# MainSch.net
KiCad netlist of a schematic drawn in Altium Designer
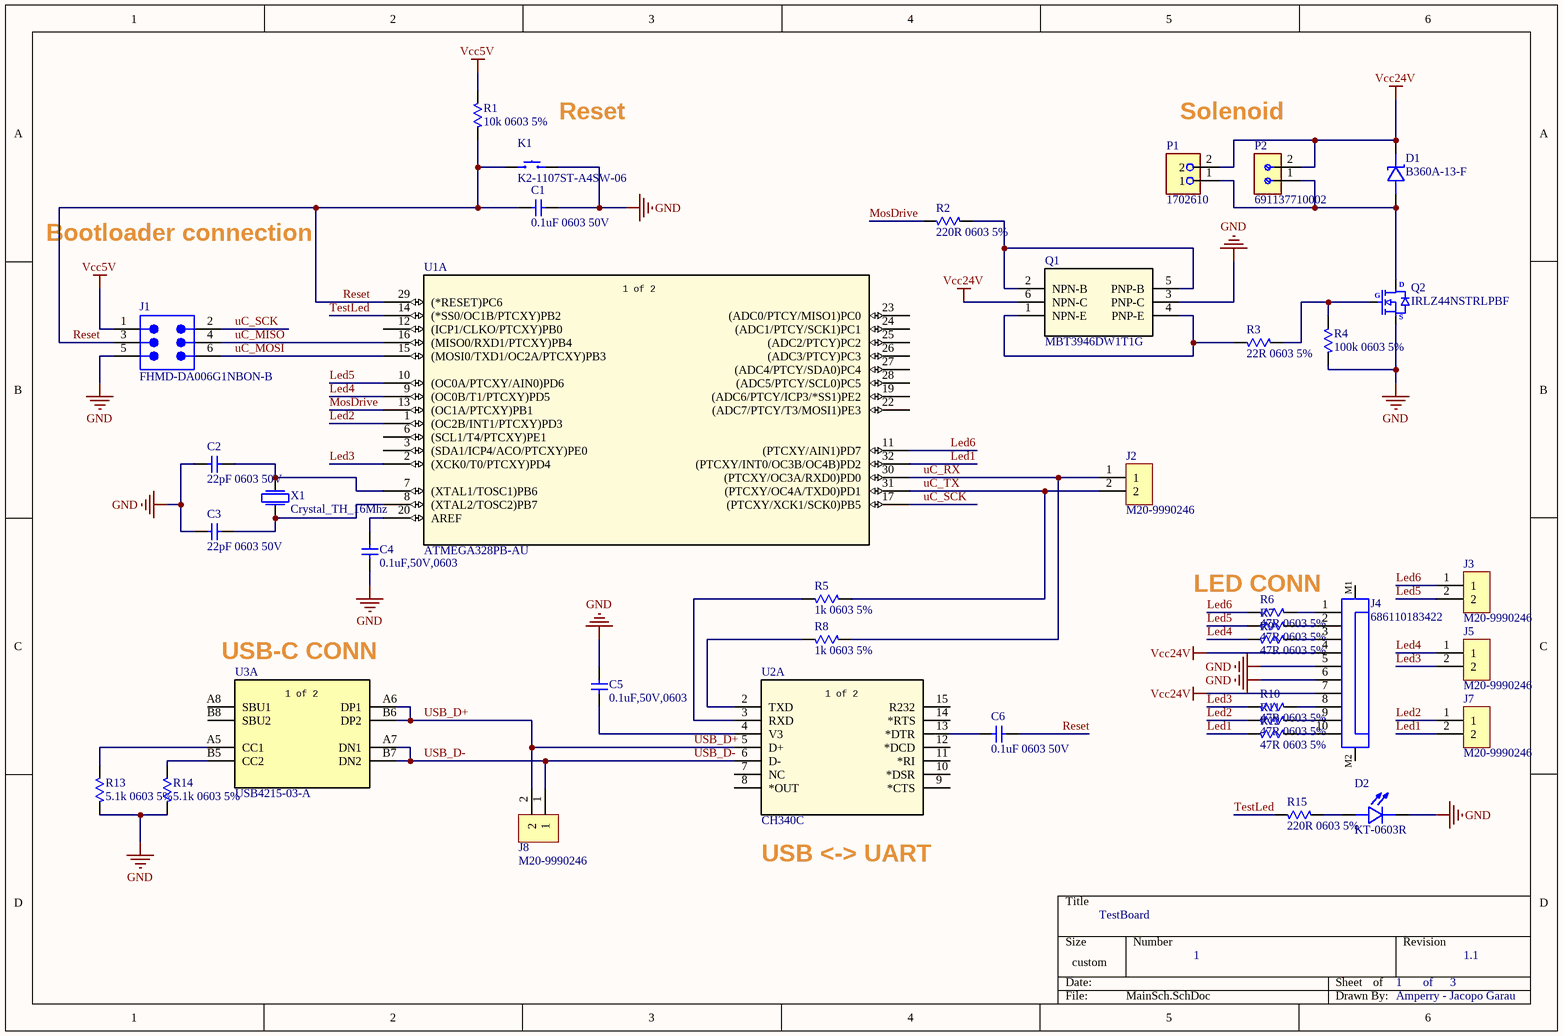
[diagram p0: MainSch.SchDoc]

(export (version "E")
  (design (tool "Eeschema 10.0.6"))
  (components
    (comp (ref "C1")
      (value "0.1uF 0603 50V")
      (footprint "CAP_0603")
      (description "50V 0.1uF (100nF) X7R ±10% 0603 Multilayer Ceramic Capacitors MLCC - SMD/SMT ROHS")
      (fields
        (field (name "MANUFACTURER PART NUMBER") "CL10B104KB8NNNC")
        (field (name "JLCPCB PART NUMBER") "C1591")
      )
      (libsource (lib "Amperry") (part "Capacitor"))
    )
    (comp (ref "C2")
      (value "22pF 0603 50V")
      (footprint "CAP_0603")
      (description "25V 10uF C0G ±5% 0603 Multilayer Ceramic Capacitors MLCC - SMD/SMT ROHS")
      (fields (field (name "VOLTAGE") "50V") (field (name "JLCPCB PART NUMBER") "C2167297"))
      (libsource (lib "Amperry") (part "Capacitor"))
    )
    (comp (ref "C3")
      (value "22pF 0603 50V")
      (footprint "CAP_0603")
      (description "25V 10uF C0G ±5% 0603 Multilayer Ceramic Capacitors MLCC - SMD/SMT ROHS")
      (fields (field (name "VOLTAGE") "50V") (field (name "JLCPCB PART NUMBER") "C2167297"))
      (libsource (lib "Amperry") (part "Capacitor"))
    )
    (comp (ref "C4")
      (value "0.1uF,50V,0603")
      (footprint "CAP_0603")
      (description "50V 0.1uF X7R 10% Pad SMD 0603 125°C T/R Ceramic Capacitor (MLCC")
      (fields
        (field (name "MANUFACTURER") "Samsung Electro-Mechanics")
        (field (name "MANUFACTURER PART NUMBER") "CL10B104KB8NNNC")
      )
      (libsource (lib "My_Integrated_Library") (part "CL10B104KB8NNNC"))
    )
    (comp (ref "C5")
      (value "0.1uF,50V,0603")
      (footprint "CAP_0603")
      (description "50V 0.1uF X7R 10% Pad SMD 0603 125°C T/R Ceramic Capacitor (MLCC")
      (fields
        (field (name "MANUFACTURER") "Samsung Electro-Mechanics")
        (field (name "MANUFACTURER PART NUMBER") "CL10B104KB8NNNC")
      )
      (libsource (lib "My_Integrated_Library") (part "CL10B104KB8NNNC"))
    )
    (comp (ref "C6")
      (value "0.1uF 0603 50V")
      (footprint "CAP_0603")
      (description "50V 0.1uF (100nF) X7R ±10% 0603 Multilayer Ceramic Capacitors MLCC - SMD/SMT ROHS")
      (fields
        (field (name "MANUFACTURER PART NUMBER") "CL10B104KB8NNNC")
        (field (name "JLCPCB PART NUMBER") "C1591")
      )
      (libsource (lib "Amperry") (part "Capacitor"))
    )
    (comp (ref "D1")
      (value "B360A-13-F")
      (footprint "SMA-DO-214AC")
      (description "60V 3.0A SURFACE MOUNT SCHOTTKY BARRIER RECTIFIER")
      (libsource (lib "Amperry") (part "Diode Schottky"))
    )
    (comp (ref "D2")
      (value "KT-0603R")
      (footprint "LED_0603")
      (description "Diode Red 20mA")
      (fields
        (field (name "MANUFACTURER PART NUMBER") "ERJ3GEYJ470V")
        (field (name "JLCPCB PART NUMBER") "C2286")
      )
      (libsource (lib "Amperry") (part "LED"))
    )
    (comp (ref "J1")
      (value "FHMD-DA006G1NBON-B")
      (footprint "Header_Female_2x3_2.54mm")
      (description "Header_Female_2x3_2.54mm")
      (fields
        (field (name "MANUFACTURER") "Sullins")
        (field (name "MANUFACTURER PART NUMBER") "PPTC032LFBN-RC")
      )
      (libsource (lib "Amperry") (part "Header_Female_2x3"))
    )
    (comp (ref "J2")
      (value "M20-9990246")
      (footprint "Header_Male_1x2_2.54mm")
      (description "Header Male 1x2 2.54mm")
      (fields (field (name "JLCPCB PART NUMBER") "C90288") (field (name "MANUFACTURER") "Harwin"))
      (libsource (lib "") (part "Header_Male_1x2_1"))
    )
    (comp (ref "J3")
      (value "M20-9990246")
      (footprint "Header_Male_1x2_2.54mm")
      (description "Header Male 1x2 2.54mm")
      (fields (field (name "JLCPCB PART NUMBER") "C90288") (field (name "MANUFACTURER") "Harwin"))
      (libsource (lib "") (part "Header_Male_1x2_1"))
    )
    (comp (ref "J4")
      (value "686110183422")
      (footprint "686110183422")
      (description "WR-FPC 1.00mm SMT Horiz. Top Cont. Low Profile")
      (fields (field (name "JLCPCB PART NUMBER") "C6095598"))
      (libsource (lib "Amperry") (part "686110183422"))
    )
    (comp (ref "J5")
      (value "M20-9990246")
      (footprint "Header_Male_1x2_2.54mm")
      (description "Header Male 1x2 2.54mm")
      (fields (field (name "JLCPCB PART NUMBER") "C90288") (field (name "MANUFACTURER") "Harwin"))
      (libsource (lib "") (part "Header_Male_1x2_1"))
    )
    (comp (ref "J7")
      (value "M20-9990246")
      (footprint "Header_Male_1x2_2.54mm")
      (description "Header Male 1x2 2.54mm")
      (fields (field (name "JLCPCB PART NUMBER") "C90288") (field (name "MANUFACTURER") "Harwin"))
      (libsource (lib "") (part "Header_Male_1x2_1"))
    )
    (comp (ref "J8")
      (value "M20-9990246")
      (footprint "Header_Male_1x2_2.54mm")
      (description "Header Male 1x2 2.54mm")
      (fields (field (name "JLCPCB PART NUMBER") "C90288") (field (name "MANUFACTURER") "Harwin"))
      (libsource (lib "Amperry") (part "Header_Male_1x2"))
    )
    (comp (ref "K1")
      (value "K2-1107ST-A4SW-06")
      (footprint "K2-1107ST-A4SW-06")
      (fields (field (name "JLCPCB PART NUMBER") "C2837195"))
      (libsource (lib "Amperry") (part "K2-1107ST-A4SW-06"))
    )
    (comp (ref "P1")
      (value "1702610")
      (footprint "1702610")
      (description "Conn PC Terminal Block 2 POS 2.5mm Solder ST Thru-Hole 4A T/R")
      (fields (field (name "VOLTAGE") "150V") (field (name "JLCPCB PART NUMBER") "C21433539"))
      (libsource (lib "Amperry") (part "1702610"))
    )
    (comp (ref "P2")
      (value "691137710002")
      (footprint "Termina_Block_1x2_5mm")
      (description "Terminal Block, 5mm Pitch, Horizontal, Pressure Clamp Glow Wire, Pcb, 2PINS, Gr")
      (fields (field (name "JLCPCB PART NUMBER") "C3703") (field (name "MANUFACTURER") "Wurth Elektronik"))
      (libsource (lib "Amperry") (part "Terminal_Block_1x2"))
    )
    (comp (ref "Q1")
      (value "MBT3946DW1T1G")
      (footprint "SOT-363")
      (description "Dual Npn+Pnp Rf Bipolar Transistor, 0.2 A, 40V, 6-PIN SC-88")
      (fields (field (name "MANUFACTURER") "onsemi") (field (name "JLCPCB PART NUMBER") "C28272"))
      (libsource (lib "Amperry") (part "MBT3946DW1T1G"))
    )
    (comp (ref "Q2")
      (value "IRLZ44NSTRLPBF")
      (footprint "D2PAK")
      (description "Mosfet, Power; N-ch; Vdss 55V; Rds(on) 0.022 Ohm; Id 47A; D2PAK; Pd 110W; Vgs +/-16V; -55")
      (fields (field (name "MANUFACTURER") "Infineon") (field (name "JLCPCB PART NUMBER") "C18212570"))
      (libsource (lib "Amperry") (part "IRLZ44N"))
    )
    (comp (ref "R1")
      (value "10k 0603 5%")
      (footprint "RES_0603")
      (description "10k Ohm 0603 5% Chip Resistor SMD")
      (fields (field (name "TOLERANCE") "5%") (field (name "JLCPCB PART NUMBER") "C25804"))
      (libsource (lib "Amperry") (part "Resistor"))
    )
    (comp (ref "R2")
      (value "220R 0603 5%")
      (footprint "RES_0603")
      (description "220 Ohm 0603 5% Chip Resistor SMD")
      (fields
        (field (name "MANUFACTURER") "Royal Ohm")
        (field (name "MANUFACTURER PART NUMBER") "0603WAJ0221T5E")
      )
      (libsource (lib "Amperry") (part "Resistor"))
    )
    (comp (ref "R3")
      (value "22R 0603 5%")
      (footprint "RES_0603")
      (description "22 Ohm 0603 1% Chip Resistor SMD")
      (fields (field (name "JLCPCB PART NUMBER") "C1203") (field (name "TOLERANCE") "5%"))
      (libsource (lib "Amperry") (part "Resistor"))
    )
    (comp (ref "R4")
      (value "100k 0603 5%")
      (footprint "RES_0603")
      (description "100k Ohm 0603 5% Chip Resistor SMD")
      (fields
        (field (name "MANUFACTURER PART NUMBER") "RC0603FR-07100KL")
        (field (name "JLCPCB PART NUMBER") "C14675")
      )
      (libsource (lib "Amperry") (part "Resistor"))
    )
    (comp (ref "R5")
      (value "1k 0603 5%")
      (footprint "RES_0603")
      (description "1k 0603 5% Chip Resistor SMD")
      (fields (field (name "JLCPCB PART NUMBER") "C14676") (field (name "TOLERANCE") "5%"))
      (libsource (lib "Amperry") (part "Resistor"))
    )
    (comp (ref "R6")
      (value "47R 0603 5%")
      (footprint "RES_0603")
      (description "47 Ohm 0603 5% Chip Resistor SMD")
      (fields (field (name "TOLERANCE") "5%") (field (name "JLCPCB PART NUMBER") "C1186"))
      (libsource (lib "Amperry") (part "Resistor"))
    )
    (comp (ref "R7")
      (value "47R 0603 5%")
      (footprint "RES_0603")
      (description "47 Ohm 0603 5% Chip Resistor SMD")
      (fields (field (name "TOLERANCE") "5%") (field (name "JLCPCB PART NUMBER") "C1186"))
      (libsource (lib "Amperry") (part "Resistor"))
    )
    (comp (ref "R8")
      (value "1k 0603 5%")
      (footprint "RES_0603")
      (description "1k 0603 5% Chip Resistor SMD")
      (fields (field (name "JLCPCB PART NUMBER") "C14676") (field (name "TOLERANCE") "5%"))
      (libsource (lib "Amperry") (part "Resistor"))
    )
    (comp (ref "R9")
      (value "47R 0603 5%")
      (footprint "RES_0603")
      (description "47 Ohm 0603 5% Chip Resistor SMD")
      (fields (field (name "TOLERANCE") "5%") (field (name "JLCPCB PART NUMBER") "C1186"))
      (libsource (lib "Amperry") (part "Resistor"))
    )
    (comp (ref "R10")
      (value "47R 0603 5%")
      (footprint "RES_0603")
      (description "47 Ohm 0603 5% Chip Resistor SMD")
      (fields (field (name "TOLERANCE") "5%") (field (name "JLCPCB PART NUMBER") "C1186"))
      (libsource (lib "Amperry") (part "Resistor"))
    )
    (comp (ref "R11")
      (value "47R 0603 5%")
      (footprint "RES_0603")
      (description "47 Ohm 0603 5% Chip Resistor SMD")
      (fields (field (name "TOLERANCE") "5%") (field (name "JLCPCB PART NUMBER") "C1186"))
      (libsource (lib "Amperry") (part "Resistor"))
    )
    (comp (ref "R12")
      (value "47R 0603 5%")
      (footprint "RES_0603")
      (description "47 Ohm 0603 5% Chip Resistor SMD")
      (fields (field (name "TOLERANCE") "5%") (field (name "JLCPCB PART NUMBER") "C1186"))
      (libsource (lib "Amperry") (part "Resistor"))
    )
    (comp (ref "R13")
      (value "5.1k 0603 5%")
      (footprint "RES_0603")
      (description "5.1k Ohm 0603 5% Chip Resistor SMD")
      (fields (field (name "TOLERANCE") "5%") (field (name "MANUFACTURER") "Yageo Group"))
      (libsource (lib "Amperry") (part "Resistor"))
    )
    (comp (ref "R14")
      (value "5.1k 0603 5%")
      (footprint "RES_0603")
      (description "5.1k Ohm 0603 5% Chip Resistor SMD")
      (fields (field (name "TOLERANCE") "5%") (field (name "MANUFACTURER") "Yageo Group"))
      (libsource (lib "Amperry") (part "Resistor"))
    )
    (comp (ref "R15")
      (value "220R 0603 5%")
      (footprint "RES_0603")
      (description "220 Ohm 0603 5% Chip Resistor SMD")
      (fields
        (field (name "MANUFACTURER") "Royal Ohm")
        (field (name "MANUFACTURER PART NUMBER") "0603WAJ0221T5E")
      )
      (libsource (lib "Amperry") (part "Resistor"))
    )
    (comp (ref "U1")
      (value "ATMEGA328PB-AU")
      (footprint "TQFP-32")
      (fields
        (field (name "JLCPCB PART NUMBER") "C618731")
        (field (name "COPYRIGHT") "Copyright (C) 2025 Ultra Librarian. All rights reserved.")
      )
      (libsource (lib "Amperry") (part "ATMEGA328PB-AU"))
    )
    (comp (ref "U2")
      (value "CH340C")
      (footprint "SOP-16")
      (description "USB to UART Serial Converter")
      (fields (field (name "JLCPCB PART NUMBER") "C84681"))
      (libsource (lib "Amperry") (part "CH340C"))
    )
    (comp (ref "U3")
      (value "USB4215-03-A")
      (footprint "USB4215-03-A")
      (description "USB-C, 12+4 Contacts 16POS Rohs Compliant: Yes")
      (fields
        (field (name "JLCPCB PART NUMBER") "C165948")
        (field (name "MANUFACTURER") "Global Connector Technology")
      )
      (libsource (lib "Amperry") (part "USB-C 16P"))
    )
    (comp (ref "X1")
      (value "Crystal_TH_16Mhz")
      (footprint "XTAL_TH_4.88mm")
      (description "Crystal, 16Mhz, Th, 11.05mm X 4.7mm Rohs Compliant")
      (fields (field (name "MANUFACTURER") "Wurth Elektronik") (field (name "JLCPCB PART NUMBER") "C6412216"))
      (libsource (lib "Amperry") (part "Crystal"))
    )
  )
  (nets
    (net (code "1") (name "/Led1") (class "Default")
      (node (ref "J7") (pin "2") (pinfunction "2_2") (pintype "passive"))
      (node (ref "R12") (pin "1") (pinfunction "1_1") (pintype "passive"))
      (node (ref "U1") (pin "32") (pinfunction "(PTCXY/INT0/OC3B/OC4B)PD2_32") (pintype "bidirectional"))
    )
    (net (code "2") (name "/Led2") (class "Default")
      (node (ref "J7") (pin "1") (pinfunction "1_1") (pintype "passive"))
      (node (ref "R11") (pin "1") (pinfunction "1_1") (pintype "passive"))
      (node (ref "U1") (pin "1") (pinfunction "(OC2B/INT1/PTCXY)PD3_1") (pintype "bidirectional"))
    )
    (net (code "3") (name "/Led3") (class "Default")
      (node (ref "J5") (pin "2") (pinfunction "2_2") (pintype "passive"))
      (node (ref "R10") (pin "1") (pinfunction "1_1") (pintype "passive"))
      (node (ref "U1") (pin "2") (pinfunction "(XCK0/T0/PTCXY)PD4_2") (pintype "bidirectional"))
    )
    (net (code "4") (name "/Led4") (class "Default")
      (node (ref "J5") (pin "1") (pinfunction "1_1") (pintype "passive"))
      (node (ref "R9") (pin "1") (pinfunction "1_1") (pintype "passive"))
      (node (ref "U1") (pin "9") (pinfunction "(OC0B/T1/PTCXY)PD5_9") (pintype "bidirectional"))
    )
    (net (code "5") (name "/Led5") (class "Default")
      (node (ref "J3") (pin "2") (pinfunction "2_2") (pintype "passive"))
      (node (ref "R7") (pin "1") (pinfunction "1_1") (pintype "passive"))
      (node (ref "U1") (pin "10") (pinfunction "(OC0A/PTCXY/AIN0)PD6_10") (pintype "bidirectional"))
    )
    (net (code "6") (name "/Led6") (class "Default")
      (node (ref "J3") (pin "1") (pinfunction "1_1") (pintype "passive"))
      (node (ref "R6") (pin "1") (pinfunction "1_1") (pintype "passive"))
      (node (ref "U1") (pin "11") (pinfunction "(PTCXY/AIN1)PD7_11") (pintype "bidirectional"))
    )
    (net (code "7") (name "/MosDrive") (class "Default")
      (node (ref "R2") (pin "1") (pinfunction "1_1") (pintype "passive"))
      (node (ref "U1") (pin "13") (pinfunction "(OC1A/PTCXY)PB1_13") (pintype "bidirectional"))
    )
    (net (code "8") (name "/Reset") (class "Default")
      (node (ref "C1") (pin "1") (pinfunction "1_1") (pintype "passive"))
      (node (ref "C6") (pin "2") (pinfunction "2_2") (pintype "passive"))
      (node (ref "J1") (pin "3") (pinfunction "3_3") (pintype "passive"))
      (node (ref "K1") (pin "1") (pinfunction "1_1") (pintype "passive"))
      (node (ref "R1") (pin "1") (pinfunction "1_1") (pintype "passive"))
      (node (ref "U1") (pin "29") (pinfunction "(*RESET)PC6_29") (pintype "bidirectional"))
    )
    (net (code "9") (name "/TestLed") (class "Default")
      (node (ref "R15") (pin "1") (pinfunction "1_1") (pintype "passive"))
      (node (ref "U1") (pin "14") (pinfunction "(*SS0/OC1B/PTCXY)PB2_14") (pintype "bidirectional"))
    )
    (net (code "10") (name "/USB_D+") (class "Default")
      (node (ref "J8") (pin "2") (pinfunction "2_2") (pintype "passive"))
      (node (ref "U2") (pin "5") (pinfunction "D+_5") (pintype "passive"))
      (node (ref "U3") (pin "A6") (pinfunction "DP1_A6") (pintype "passive"))
      (node (ref "U3") (pin "B6") (pinfunction "DP2_B6") (pintype "passive"))
    )
    (net (code "11") (name "/USB_D-") (class "Default")
      (node (ref "J8") (pin "1") (pinfunction "1_1") (pintype "passive"))
      (node (ref "U2") (pin "6") (pinfunction "D-_6") (pintype "passive"))
      (node (ref "U3") (pin "A7") (pinfunction "DN1_A7") (pintype "passive"))
      (node (ref "U3") (pin "B7") (pinfunction "DN2_B7") (pintype "passive"))
    )
    (net (code "12") (name "/uC_MISO") (class "Default")
      (node (ref "J1") (pin "4") (pinfunction "4_4") (pintype "passive"))
      (node (ref "U1") (pin "16") (pinfunction "(MISO0/RXD1/PTCXY)PB4_16") (pintype "bidirectional"))
    )
    (net (code "13") (name "/uC_MOSI") (class "Default")
      (node (ref "J1") (pin "6") (pinfunction "6_6") (pintype "passive"))
      (node (ref "U1") (pin "15") (pinfunction "(MOSI0/TXD1/OC2A/PTCXY)PB3_15") (pintype "bidirectional"))
    )
    (net (code "14") (name "/uC_RX") (class "Default")
      (node (ref "J2") (pin "1") (pinfunction "1_1") (pintype "passive"))
      (node (ref "R8") (pin "2") (pinfunction "2_2") (pintype "passive"))
      (node (ref "U1") (pin "30") (pinfunction "(PTCXY/OC3A/RXD0)PD0_30") (pintype "bidirectional"))
    )
    (net (code "15") (name "/uC_SCK") (class "Default")
      (node (ref "J1") (pin "2") (pinfunction "2_2") (pintype "passive"))
      (node (ref "U1") (pin "17") (pinfunction "(PTCXY/XCK1/SCK0)PB5_17") (pintype "bidirectional"))
    )
    (net (code "16") (name "/uC_TX") (class "Default")
      (node (ref "J2") (pin "2") (pinfunction "2_2") (pintype "passive"))
      (node (ref "R5") (pin "2") (pinfunction "2_2") (pintype "passive"))
      (node (ref "U1") (pin "31") (pinfunction "(PTCXY/OC4A/TXD0)PD1_31") (pintype "bidirectional"))
    )
    (net (code "17") (name "GND") (class "Default")
      (node (ref "C1") (pin "2") (pinfunction "2_2") (pintype "passive"))
      (node (ref "C2") (pin "1") (pinfunction "1_1") (pintype "passive"))
      (node (ref "C3") (pin "1") (pinfunction "1_1") (pintype "passive"))
      (node (ref "C4") (pin "1") (pinfunction "1_1") (pintype "passive"))
      (node (ref "C5") (pin "1") (pinfunction "1_1") (pintype "passive"))
      (node (ref "D2") (pin "K") (pinfunction "K_K") (pintype "passive"))
      (node (ref "J1") (pin "5") (pinfunction "5_5") (pintype "passive"))
      (node (ref "J4") (pin "5") (pinfunction "5_5") (pintype "passive"))
      (node (ref "J4") (pin "6") (pinfunction "6_6") (pintype "passive"))
      (node (ref "K1") (pin "2") (pinfunction "2_2") (pintype "passive"))
      (node (ref "Q1") (pin "3") (pinfunction "PNP-C_3") (pintype "passive"))
      (node (ref "Q2") (pin "3") (pinfunction "S_3") (pintype "passive"))
      (node (ref "R13") (pin "1") (pinfunction "1_1") (pintype "passive"))
      (node (ref "R14") (pin "1") (pinfunction "1_1") (pintype "passive"))
      (node (ref "R4") (pin "1") (pinfunction "1_1") (pintype "passive"))
    )
    (net (code "18") (name "Net-(D2-PadA)") (class "Default")
      (node (ref "D2") (pin "A") (pinfunction "A_A") (pintype "passive"))
      (node (ref "R15") (pin "2") (pinfunction "2_2") (pintype "passive"))
    )
    (net (code "19") (name "Net-(J4-Pad1)") (class "Default")
      (node (ref "J4") (pin "1") (pinfunction "1_1") (pintype "passive"))
      (node (ref "R6") (pin "2") (pinfunction "2_2") (pintype "passive"))
    )
    (net (code "20") (name "Net-(J4-Pad2)") (class "Default")
      (node (ref "J4") (pin "2") (pinfunction "2_2") (pintype "passive"))
      (node (ref "R7") (pin "2") (pinfunction "2_2") (pintype "passive"))
    )
    (net (code "21") (name "Net-(J4-Pad3)") (class "Default")
      (node (ref "J4") (pin "3") (pinfunction "3_3") (pintype "passive"))
      (node (ref "R9") (pin "2") (pinfunction "2_2") (pintype "passive"))
    )
    (net (code "22") (name "Net-(J4-Pad8)") (class "Default")
      (node (ref "J4") (pin "8") (pinfunction "8_8") (pintype "passive"))
      (node (ref "R10") (pin "2") (pinfunction "2_2") (pintype "passive"))
    )
    (net (code "23") (name "Net-(J4-Pad9)") (class "Default")
      (node (ref "J4") (pin "9") (pinfunction "9_9") (pintype "passive"))
      (node (ref "R11") (pin "2") (pinfunction "2_2") (pintype "passive"))
    )
    (net (code "24") (name "Net-(J4-Pad10)") (class "Default")
      (node (ref "J4") (pin "10") (pinfunction "10_10") (pintype "passive"))
      (node (ref "R12") (pin "2") (pinfunction "2_2") (pintype "passive"))
    )
    (net (code "25") (name "Net-(Q1-NPN-B)") (class "Default")
      (node (ref "Q1") (pin "2") (pinfunction "NPN-B_2") (pintype "passive"))
      (node (ref "Q1") (pin "5") (pinfunction "PNP-B_5") (pintype "passive"))
      (node (ref "R2") (pin "2") (pinfunction "2_2") (pintype "passive"))
    )
    (net (code "26") (name "Net-(Q1-NPN-E)") (class "Default")
      (node (ref "Q1") (pin "1") (pinfunction "NPN-E_1") (pintype "passive"))
      (node (ref "Q1") (pin "4") (pinfunction "PNP-E_4") (pintype "passive"))
      (node (ref "R3") (pin "1") (pinfunction "1_1") (pintype "passive"))
    )
    (net (code "27") (name "Net-(Q2-D)") (class "Default")
      (node (ref "D1") (pin "A") (pinfunction "A_A") (pintype "passive"))
      (node (ref "P1") (pin "1") (pinfunction "1_1") (pintype "passive"))
      (node (ref "P2") (pin "1") (pinfunction "1_1") (pintype "passive"))
      (node (ref "Q2") (pin "2") (pinfunction "D_2") (pintype "passive"))
    )
    (net (code "28") (name "Net-(Q2-G)") (class "Default")
      (node (ref "Q2") (pin "1") (pinfunction "G_1") (pintype "passive"))
      (node (ref "R3") (pin "2") (pinfunction "2_2") (pintype "passive"))
      (node (ref "R4") (pin "2") (pinfunction "2_2") (pintype "passive"))
    )
    (net (code "29") (name "Net-(U1A-(XTAL1{slash}TOSC1)PB6)") (class "Default")
      (node (ref "C2") (pin "2") (pinfunction "2_2") (pintype "passive"))
      (node (ref "U1") (pin "7") (pinfunction "(XTAL1/TOSC1)PB6_7") (pintype "bidirectional"))
      (node (ref "X1") (pin "2") (pinfunction "2_2") (pintype "passive"))
    )
    (net (code "30") (name "Net-(U1A-(XTAL2{slash}TOSC2)PB7)") (class "Default")
      (node (ref "C3") (pin "2") (pinfunction "2_2") (pintype "passive"))
      (node (ref "U1") (pin "8") (pinfunction "(XTAL2/TOSC2)PB7_8") (pintype "bidirectional"))
      (node (ref "X1") (pin "1") (pinfunction "1_1") (pintype "passive"))
    )
    (net (code "31") (name "Net-(U1A-AREF)") (class "Default")
      (node (ref "C4") (pin "2") (pinfunction "2_2") (pintype "passive"))
      (node (ref "U1") (pin "20") (pinfunction "AREF_20") (pintype "bidirectional"))
    )
    (net (code "32") (name "Net-(U2A-*DTR)") (class "Default")
      (node (ref "C6") (pin "1") (pinfunction "1_1") (pintype "passive"))
      (node (ref "U2") (pin "13") (pinfunction "*DTR_13") (pintype "open_emitter"))
    )
    (net (code "33") (name "Net-(U2A-RXD)") (class "Default")
      (node (ref "R5") (pin "1") (pinfunction "1_1") (pintype "passive"))
      (node (ref "U2") (pin "3") (pinfunction "RXD_3") (pintype "passive"))
    )
    (net (code "34") (name "Net-(U2A-TXD)") (class "Default")
      (node (ref "R8") (pin "1") (pinfunction "1_1") (pintype "passive"))
      (node (ref "U2") (pin "2") (pinfunction "TXD_2") (pintype "passive"))
    )
    (net (code "35") (name "Net-(U2A-V3)") (class "Default")
      (node (ref "C5") (pin "2") (pinfunction "2_2") (pintype "passive"))
      (node (ref "U2") (pin "4") (pinfunction "V3_4") (pintype "passive"))
    )
    (net (code "36") (name "Net-(U3A-CC1)") (class "Default")
      (node (ref "R13") (pin "2") (pinfunction "2_2") (pintype "passive"))
      (node (ref "U3") (pin "A5") (pinfunction "CC1_A5") (pintype "passive"))
    )
    (net (code "37") (name "Net-(U3A-CC2)") (class "Default")
      (node (ref "R14") (pin "2") (pinfunction "2_2") (pintype "passive"))
      (node (ref "U3") (pin "B5") (pinfunction "CC2_B5") (pintype "passive"))
    )
    (net (code "38") (name "Vcc5V") (class "Default")
      (node (ref "J1") (pin "1") (pinfunction "1_1") (pintype "passive"))
      (node (ref "R1") (pin "2") (pinfunction "2_2") (pintype "passive"))
    )
    (net (code "39") (name "Vcc24V") (class "Default")
      (node (ref "D1") (pin "K") (pinfunction "K_K") (pintype "passive"))
      (node (ref "J4") (pin "4") (pinfunction "4_4") (pintype "passive"))
      (node (ref "J4") (pin "7") (pinfunction "7_7") (pintype "passive"))
      (node (ref "P1") (pin "2") (pinfunction "2_2") (pintype "passive"))
      (node (ref "P2") (pin "2") (pinfunction "2_2") (pintype "passive"))
      (node (ref "Q1") (pin "6") (pinfunction "NPN-C_6") (pintype "passive"))
    )
    (net (code "40") (name "unconnected-(J4-PadM1)") (class "Default")
      (node (ref "J4") (pin "M1") (pinfunction "M1_M1") (pintype "passive"))
    )
    (net (code "41") (name "unconnected-(J4-PadM2)") (class "Default")
      (node (ref "J4") (pin "M2") (pinfunction "M2_M2") (pintype "passive"))
    )
    (net (code "42") (name "unconnected-(U1A-(ADC0{slash}PTCY{slash}MISO1)PC0-Pad23)") (class "Default")
      (node (ref "U1") (pin "23") (pinfunction "(ADC0/PTCY/MISO1)PC0_23") (pintype "bidirectional"))
    )
    (net (code "43") (name "unconnected-(U1A-(ADC1{slash}PTCY{slash}SCK1)PC1-Pad24)") (class "Default")
      (node (ref "U1") (pin "24") (pinfunction "(ADC1/PTCY/SCK1)PC1_24") (pintype "bidirectional"))
    )
    (net (code "44") (name "unconnected-(U1A-(ADC2{slash}PTCY)PC2-Pad25)") (class "Default")
      (node (ref "U1") (pin "25") (pinfunction "(ADC2/PTCY)PC2_25") (pintype "bidirectional"))
    )
    (net (code "45") (name "unconnected-(U1A-(ADC3{slash}PTCY)PC3-Pad26)") (class "Default")
      (node (ref "U1") (pin "26") (pinfunction "(ADC3/PTCY)PC3_26") (pintype "bidirectional"))
    )
    (net (code "46") (name "unconnected-(U1A-(ADC4{slash}PTCY{slash}SDA0)PC4-Pad27)") (class "Default")
      (node (ref "U1") (pin "27") (pinfunction "(ADC4/PTCY/SDA0)PC4_27") (pintype "bidirectional"))
    )
    (net (code "47") (name "unconnected-(U1A-(ADC5{slash}PTCY{slash}SCL0)PC5-Pad28)") (class "Default")
      (node (ref "U1") (pin "28") (pinfunction "(ADC5/PTCY/SCL0)PC5_28") (pintype "bidirectional"))
    )
    (net (code "48") (name "unconnected-(U1A-(ADC6{slash}PTCY{slash}ICP3{slash}*SS1)PE2-Pad19)") (class "Default")
      (node (ref "U1") (pin "19") (pinfunction "(ADC6/PTCY/ICP3/*SS1)PE2_19") (pintype "bidirectional"))
    )
    (net (code "49") (name "unconnected-(U1A-(ADC7{slash}PTCY{slash}T3{slash}MOSI1)PE3-Pad22)") (class "Default")
      (node (ref "U1") (pin "22") (pinfunction "(ADC7/PTCY/T3/MOSI1)PE3_22") (pintype "bidirectional"))
    )
    (net (code "50") (name "unconnected-(U1A-(ICP1{slash}CLKO{slash}PTCXY)PB0-Pad12)") (class "Default")
      (node (ref "U1") (pin "12") (pinfunction "(ICP1/CLKO/PTCXY)PB0_12") (pintype "bidirectional"))
    )
    (net (code "51") (name "unconnected-(U1A-(SCL1{slash}T4{slash}PTCXY)PE1-Pad6)") (class "Default")
      (node (ref "U1") (pin "6") (pinfunction "(SCL1/T4/PTCXY)PE1_6") (pintype "bidirectional"))
    )
    (net (code "52") (name "unconnected-(U1A-(SDA1{slash}ICP4{slash}ACO{slash}PTCXY)PE0-Pad3)") (class "Default")
      (node (ref "U1") (pin "3") (pinfunction "(SDA1/ICP4/ACO/PTCXY)PE0_3") (pintype "bidirectional"))
    )
    (net (code "53") (name "unconnected-(U2A-*CTS-Pad9)") (class "Default")
      (node (ref "U2") (pin "9") (pinfunction "*CTS_9") (pintype "passive"))
    )
    (net (code "54") (name "unconnected-(U2A-*DCD-Pad12)") (class "Default")
      (node (ref "U2") (pin "12") (pinfunction "*DCD_12") (pintype "power_in"))
    )
    (net (code "55") (name "unconnected-(U2A-*DSR-Pad10)") (class "Default")
      (node (ref "U2") (pin "10") (pinfunction "*DSR_10") (pintype "passive"))
    )
    (net (code "56") (name "unconnected-(U2A-*OUT-Pad8)") (class "Default")
      (node (ref "U2") (pin "8") (pinfunction "*OUT_8") (pintype "passive"))
    )
    (net (code "57") (name "unconnected-(U2A-*RI-Pad11)") (class "Default")
      (node (ref "U2") (pin "11") (pinfunction "*RI_11") (pintype "passive"))
    )
    (net (code "58") (name "unconnected-(U2A-*RTS-Pad14)") (class "Default")
      (node (ref "U2") (pin "14") (pinfunction "*RTS_14") (pintype "passive"))
    )
    (net (code "59") (name "unconnected-(U2A-NC-Pad7)") (class "Default")
      (node (ref "U2") (pin "7") (pinfunction "NC_7") (pintype "passive"))
    )
    (net (code "60") (name "unconnected-(U2A-R232-Pad15)") (class "Default")
      (node (ref "U2") (pin "15") (pinfunction "R232_15") (pintype "passive"))
    )
    (net (code "61") (name "unconnected-(U3A-SBU1-PadA8)") (class "Default")
      (node (ref "U3") (pin "A8") (pinfunction "SBU1_A8") (pintype "passive"))
    )
    (net (code "62") (name "unconnected-(U3A-SBU2-PadB8)") (class "Default")
      (node (ref "U3") (pin "B8") (pinfunction "SBU2_B8") (pintype "passive"))
    )
  )
)
